# 33_PP0_CONFIG.net
KiCad netlist of a schematic drawn in Altium Designer
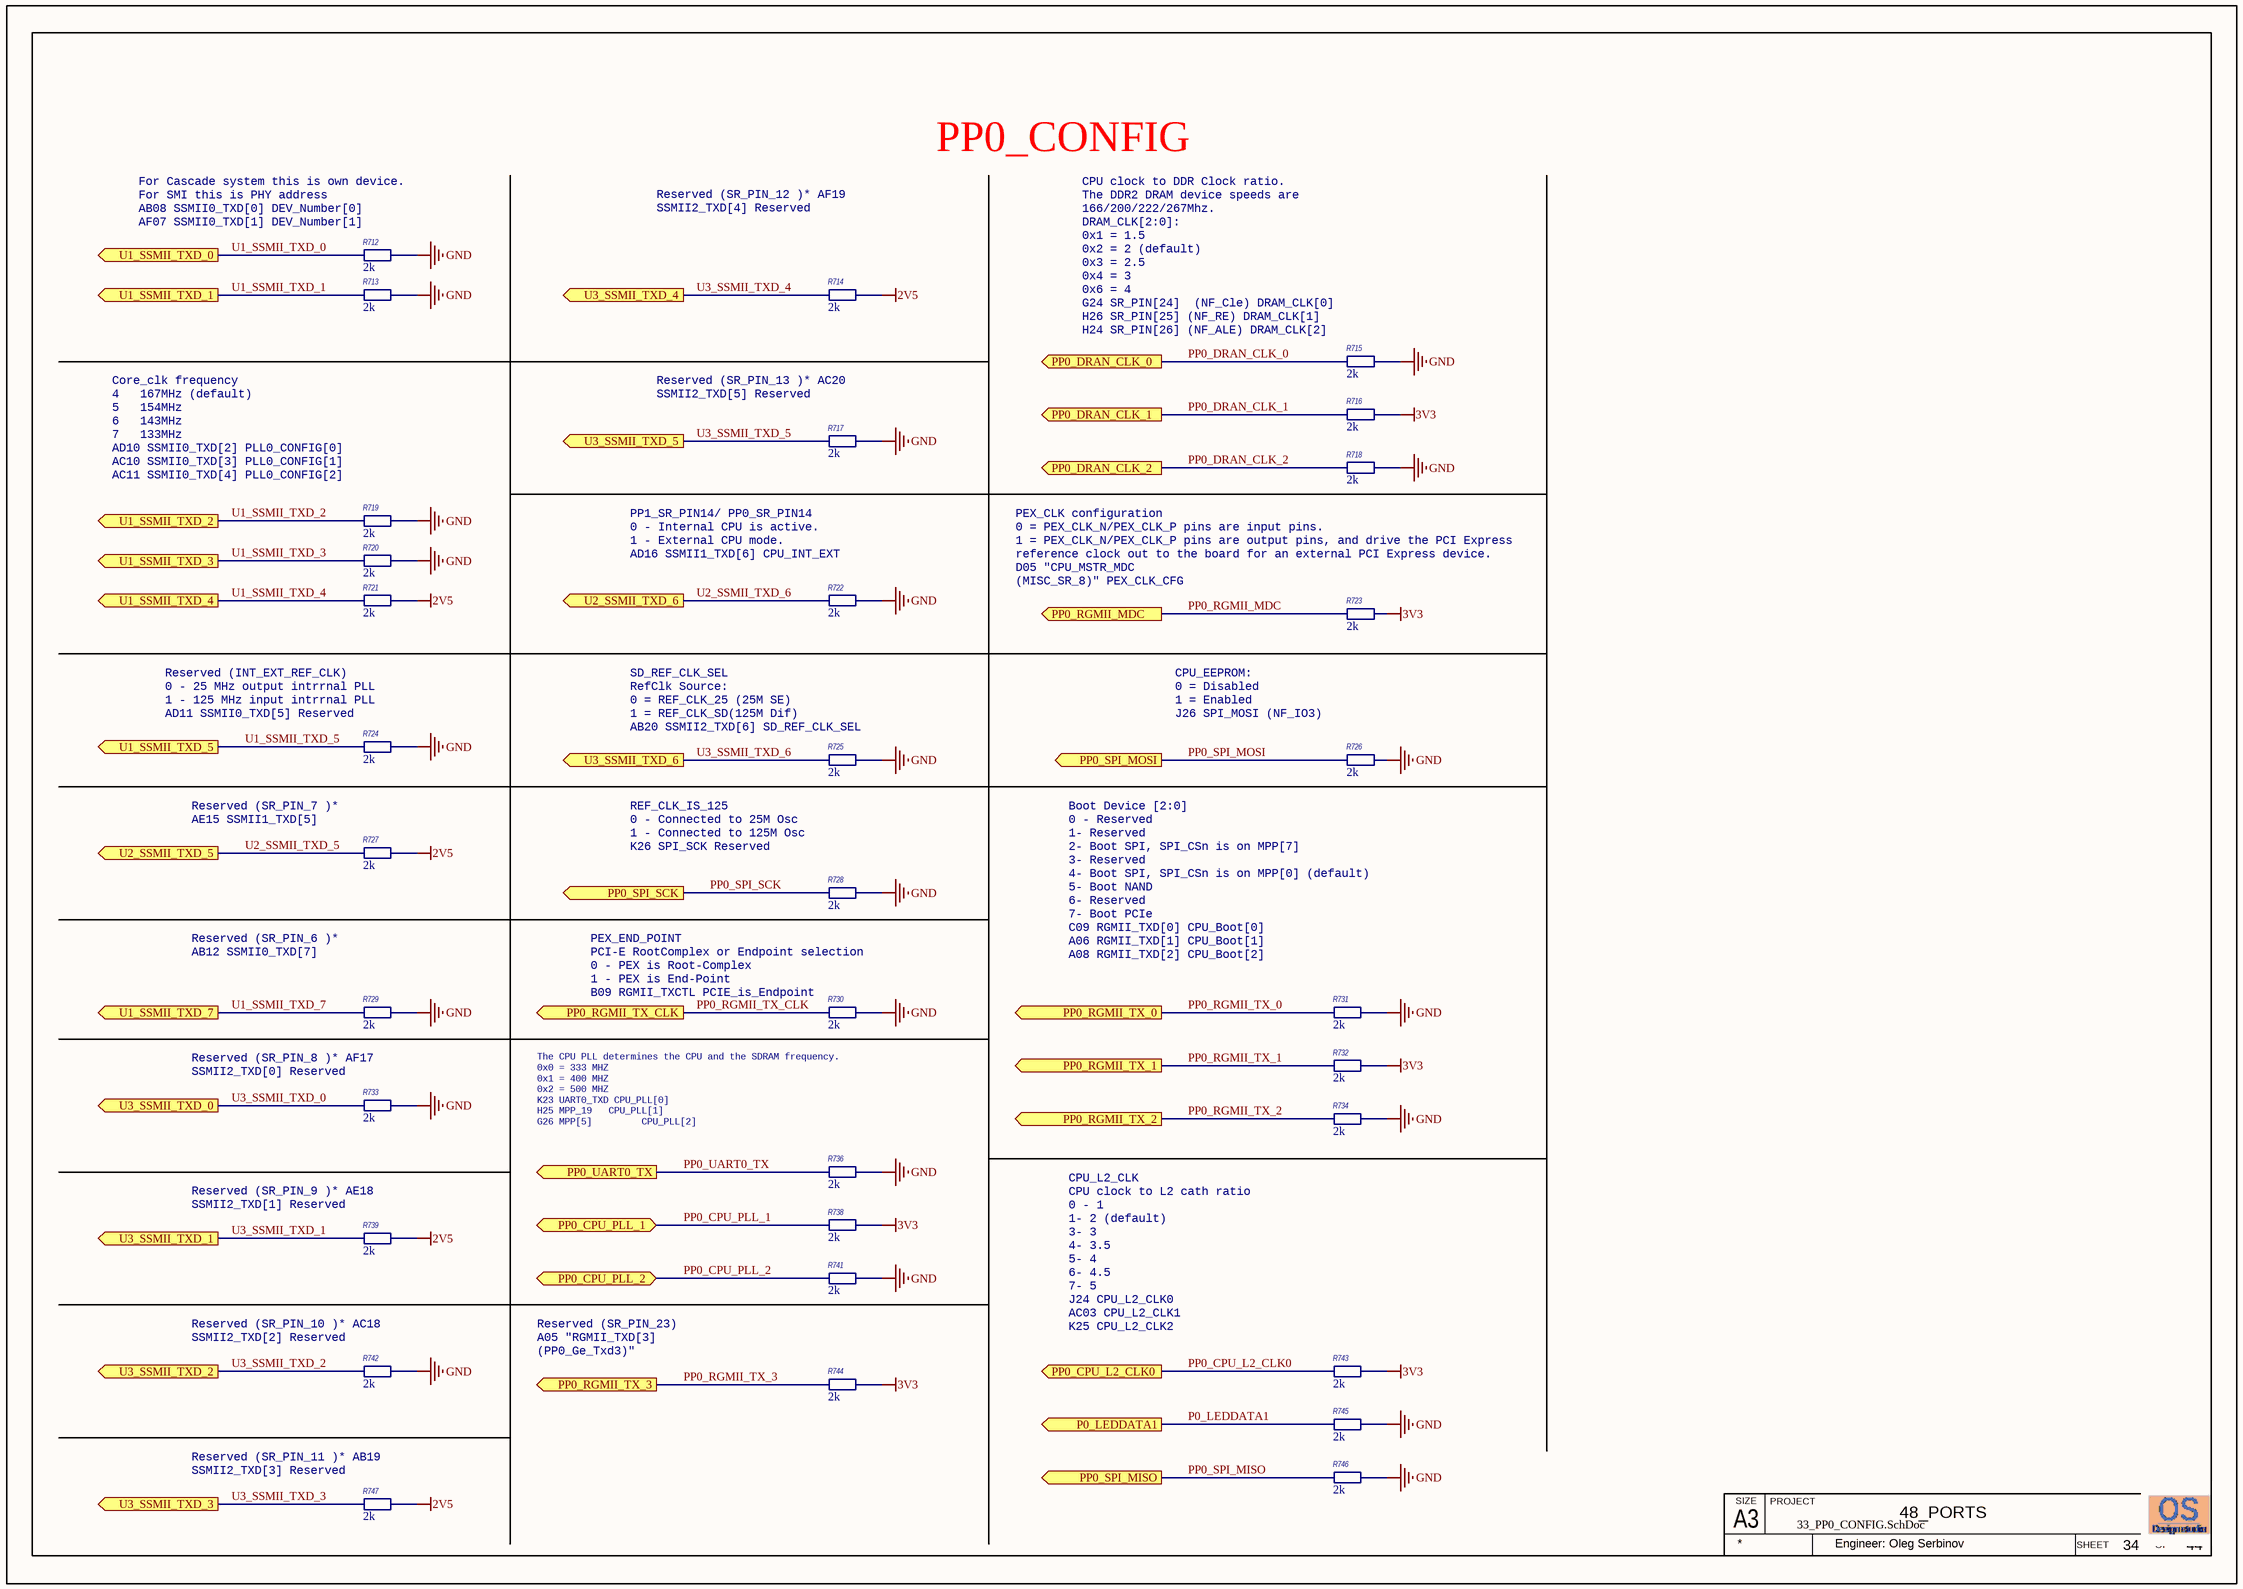
[diagram p0: 33_PP0_CONFIG.SchDoc]

(export (version "E")
  (design (tool "Eeschema 10.0.6"))
  (components
    (comp (ref "R712")
      (value "ERJ-2RKF2001X")
      (footprint "R0402_IPC High Density")
      (description "R0402, 2k 1%")
      (fields
        (field (name "TOLERANCE") "±1%")
        (field (name "MANUFACTURER") "Panasonic")
        (field (name "RESISTANCE (OHMS)") "2k")
      )
      (libsource (lib "RESISTOR") (part "ERJ-2RKF2001X"))
    )
    (comp (ref "R713")
      (value "ERJ-2RKF2001X")
      (footprint "R0402_IPC High Density")
      (description "R0402, 2k 1%")
      (fields
        (field (name "TOLERANCE") "±1%")
        (field (name "MANUFACTURER") "Panasonic")
        (field (name "RESISTANCE (OHMS)") "2k")
      )
      (libsource (lib "RESISTOR") (part "ERJ-2RKF2001X"))
    )
    (comp (ref "R714")
      (value "ERJ-2RKF2001X")
      (footprint "R0402_IPC High Density")
      (description "R0402, 2k 1%")
      (fields
        (field (name "TOLERANCE") "±1%")
        (field (name "MANUFACTURER") "Panasonic")
        (field (name "RESISTANCE (OHMS)") "2k")
      )
      (libsource (lib "RESISTOR") (part "ERJ-2RKF2001X"))
    )
    (comp (ref "R715")
      (value "ERJ-2RKF2001X")
      (footprint "R0402_IPC High Density")
      (description "R0402, 2k 1%")
      (fields
        (field (name "TOLERANCE") "±1%")
        (field (name "MANUFACTURER") "Panasonic")
        (field (name "RESISTANCE (OHMS)") "2k")
      )
      (libsource (lib "RESISTOR") (part "ERJ-2RKF2001X"))
    )
    (comp (ref "R716")
      (value "ERJ-2RKF2001X")
      (footprint "R0402_IPC High Density")
      (description "R0402, 2k 1%")
      (fields
        (field (name "TOLERANCE") "±1%")
        (field (name "MANUFACTURER") "Panasonic")
        (field (name "RESISTANCE (OHMS)") "2k")
      )
      (libsource (lib "RESISTOR") (part "ERJ-2RKF2001X"))
    )
    (comp (ref "R717")
      (value "ERJ-2RKF2001X")
      (footprint "R0402_IPC High Density")
      (description "R0402, 2k 1%")
      (fields
        (field (name "TOLERANCE") "±1%")
        (field (name "MANUFACTURER") "Panasonic")
        (field (name "RESISTANCE (OHMS)") "2k")
      )
      (libsource (lib "RESISTOR") (part "ERJ-2RKF2001X"))
    )
    (comp (ref "R718")
      (value "ERJ-2RKF2001X")
      (footprint "R0402_IPC High Density")
      (description "R0402, 2k 1%")
      (fields
        (field (name "TOLERANCE") "±1%")
        (field (name "MANUFACTURER") "Panasonic")
        (field (name "RESISTANCE (OHMS)") "2k")
      )
      (libsource (lib "RESISTOR") (part "ERJ-2RKF2001X"))
    )
    (comp (ref "R719")
      (value "ERJ-2RKF2001X")
      (footprint "R0402_IPC High Density")
      (description "R0402, 2k 1%")
      (fields
        (field (name "TOLERANCE") "±1%")
        (field (name "MANUFACTURER") "Panasonic")
        (field (name "RESISTANCE (OHMS)") "2k")
      )
      (libsource (lib "RESISTOR") (part "ERJ-2RKF2001X"))
    )
    (comp (ref "R720")
      (value "ERJ-2RKF2001X")
      (footprint "R0402_IPC High Density")
      (description "R0402, 2k 1%")
      (fields
        (field (name "TOLERANCE") "±1%")
        (field (name "MANUFACTURER") "Panasonic")
        (field (name "RESISTANCE (OHMS)") "2k")
      )
      (libsource (lib "RESISTOR") (part "ERJ-2RKF2001X"))
    )
    (comp (ref "R721")
      (value "ERJ-2RKF2001X")
      (footprint "R0402_IPC High Density")
      (description "R0402, 2k 1%")
      (fields
        (field (name "TOLERANCE") "±1%")
        (field (name "MANUFACTURER") "Panasonic")
        (field (name "RESISTANCE (OHMS)") "2k")
      )
      (libsource (lib "RESISTOR") (part "ERJ-2RKF2001X"))
    )
    (comp (ref "R722")
      (value "ERJ-2RKF2001X")
      (footprint "R0402_IPC High Density")
      (description "R0402, 2k 1%")
      (fields
        (field (name "TOLERANCE") "±1%")
        (field (name "MANUFACTURER") "Panasonic")
        (field (name "RESISTANCE (OHMS)") "2k")
      )
      (libsource (lib "RESISTOR") (part "ERJ-2RKF2001X"))
    )
    (comp (ref "R723")
      (value "ERJ-2RKF2001X")
      (footprint "R0402_IPC High Density")
      (description "R0402, 2k 1%")
      (fields
        (field (name "TOLERANCE") "±1%")
        (field (name "MANUFACTURER") "Panasonic")
        (field (name "RESISTANCE (OHMS)") "2k")
      )
      (libsource (lib "RESISTOR") (part "ERJ-2RKF2001X"))
    )
    (comp (ref "R724")
      (value "ERJ-2RKF2001X")
      (footprint "R0402_IPC High Density")
      (description "R0402, 2k 1%")
      (fields
        (field (name "TOLERANCE") "±1%")
        (field (name "MANUFACTURER") "Panasonic")
        (field (name "RESISTANCE (OHMS)") "2k")
      )
      (libsource (lib "RESISTOR") (part "ERJ-2RKF2001X"))
    )
    (comp (ref "R725")
      (value "ERJ-2RKF2001X")
      (footprint "R0402_IPC High Density")
      (description "R0402, 2k 1%")
      (fields
        (field (name "TOLERANCE") "±1%")
        (field (name "MANUFACTURER") "Panasonic")
        (field (name "RESISTANCE (OHMS)") "2k")
      )
      (libsource (lib "RESISTOR") (part "ERJ-2RKF2001X"))
    )
    (comp (ref "R726")
      (value "ERJ-2RKF2001X")
      (footprint "R0402_IPC High Density")
      (description "R0402, 2k 1%")
      (fields
        (field (name "TOLERANCE") "±1%")
        (field (name "MANUFACTURER") "Panasonic")
        (field (name "RESISTANCE (OHMS)") "2k")
      )
      (libsource (lib "RESISTOR") (part "ERJ-2RKF2001X"))
    )
    (comp (ref "R727")
      (value "ERJ-2RKF2001X")
      (footprint "R0402_IPC High Density")
      (description "R0402, 2k 1%")
      (fields
        (field (name "TOLERANCE") "±1%")
        (field (name "MANUFACTURER") "Panasonic")
        (field (name "RESISTANCE (OHMS)") "2k")
      )
      (libsource (lib "RESISTOR") (part "ERJ-2RKF2001X"))
    )
    (comp (ref "R728")
      (value "ERJ-2RKF2001X")
      (footprint "R0402_IPC High Density")
      (description "R0402, 2k 1%")
      (fields
        (field (name "TOLERANCE") "±1%")
        (field (name "MANUFACTURER") "Panasonic")
        (field (name "RESISTANCE (OHMS)") "2k")
      )
      (libsource (lib "RESISTOR") (part "ERJ-2RKF2001X"))
    )
    (comp (ref "R729")
      (value "ERJ-2RKF2001X")
      (footprint "R0402_IPC High Density")
      (description "R0402, 2k 1%")
      (fields
        (field (name "TOLERANCE") "±1%")
        (field (name "MANUFACTURER") "Panasonic")
        (field (name "RESISTANCE (OHMS)") "2k")
      )
      (libsource (lib "RESISTOR") (part "ERJ-2RKF2001X"))
    )
    (comp (ref "R730")
      (value "ERJ-2RKF2001X")
      (footprint "R0402_IPC High Density")
      (description "R0402, 2k 1%")
      (fields
        (field (name "TOLERANCE") "±1%")
        (field (name "MANUFACTURER") "Panasonic")
        (field (name "RESISTANCE (OHMS)") "2k")
      )
      (libsource (lib "RESISTOR") (part "ERJ-2RKF2001X"))
    )
    (comp (ref "R731")
      (value "ERJ-2RKF2001X")
      (footprint "R0402_IPC High Density")
      (description "R0402, 2k 1%")
      (fields
        (field (name "TOLERANCE") "±1%")
        (field (name "MANUFACTURER") "Panasonic")
        (field (name "RESISTANCE (OHMS)") "2k")
      )
      (libsource (lib "RESISTOR") (part "ERJ-2RKF2001X"))
    )
    (comp (ref "R732")
      (value "ERJ-2RKF2001X")
      (footprint "R0402_IPC High Density")
      (description "R0402, 2k 1%")
      (fields
        (field (name "TOLERANCE") "±1%")
        (field (name "MANUFACTURER") "Panasonic")
        (field (name "RESISTANCE (OHMS)") "2k")
      )
      (libsource (lib "RESISTOR") (part "ERJ-2RKF2001X"))
    )
    (comp (ref "R733")
      (value "ERJ-2RKF2001X")
      (footprint "R0402_IPC High Density")
      (description "R0402, 2k 1%")
      (fields
        (field (name "TOLERANCE") "±1%")
        (field (name "MANUFACTURER") "Panasonic")
        (field (name "RESISTANCE (OHMS)") "2k")
      )
      (libsource (lib "RESISTOR") (part "ERJ-2RKF2001X"))
    )
    (comp (ref "R734")
      (value "ERJ-2RKF2001X")
      (footprint "R0402_IPC High Density")
      (description "R0402, 2k 1%")
      (fields
        (field (name "TOLERANCE") "±1%")
        (field (name "MANUFACTURER") "Panasonic")
        (field (name "RESISTANCE (OHMS)") "2k")
      )
      (libsource (lib "RESISTOR") (part "ERJ-2RKF2001X"))
    )
    (comp (ref "R736")
      (value "ERJ-2RKF2001X")
      (footprint "R0402_IPC High Density")
      (description "R0402, 2k 1%")
      (fields
        (field (name "TOLERANCE") "±1%")
        (field (name "MANUFACTURER") "Panasonic")
        (field (name "RESISTANCE (OHMS)") "2k")
      )
      (libsource (lib "RESISTOR") (part "ERJ-2RKF2001X"))
    )
    (comp (ref "R738")
      (value "ERJ-2RKF2001X")
      (footprint "R0402_IPC High Density")
      (description "R0402, 2k 1%")
      (fields
        (field (name "TOLERANCE") "±1%")
        (field (name "MANUFACTURER") "Panasonic")
        (field (name "RESISTANCE (OHMS)") "2k")
      )
      (libsource (lib "RESISTOR") (part "ERJ-2RKF2001X"))
    )
    (comp (ref "R739")
      (value "ERJ-2RKF2001X")
      (footprint "R0402_IPC High Density")
      (description "R0402, 2k 1%")
      (fields
        (field (name "TOLERANCE") "±1%")
        (field (name "MANUFACTURER") "Panasonic")
        (field (name "RESISTANCE (OHMS)") "2k")
      )
      (libsource (lib "RESISTOR") (part "ERJ-2RKF2001X"))
    )
    (comp (ref "R741")
      (value "ERJ-2RKF2001X")
      (footprint "R0402_IPC High Density")
      (description "R0402, 2k 1%")
      (fields
        (field (name "TOLERANCE") "±1%")
        (field (name "MANUFACTURER") "Panasonic")
        (field (name "RESISTANCE (OHMS)") "2k")
      )
      (libsource (lib "RESISTOR") (part "ERJ-2RKF2001X"))
    )
    (comp (ref "R742")
      (value "ERJ-2RKF2001X")
      (footprint "R0402_IPC High Density")
      (description "R0402, 2k 1%")
      (fields
        (field (name "TOLERANCE") "±1%")
        (field (name "MANUFACTURER") "Panasonic")
        (field (name "RESISTANCE (OHMS)") "2k")
      )
      (libsource (lib "RESISTOR") (part "ERJ-2RKF2001X"))
    )
    (comp (ref "R743")
      (value "ERJ-2RKF2001X")
      (footprint "R0402_IPC High Density")
      (description "R0402, 2k 1%")
      (fields
        (field (name "TOLERANCE") "±1%")
        (field (name "MANUFACTURER") "Panasonic")
        (field (name "RESISTANCE (OHMS)") "2k")
      )
      (libsource (lib "RESISTOR") (part "ERJ-2RKF2001X"))
    )
    (comp (ref "R744")
      (value "ERJ-2RKF2001X")
      (footprint "R0402_IPC High Density")
      (description "R0402, 2k 1%")
      (fields
        (field (name "TOLERANCE") "±1%")
        (field (name "MANUFACTURER") "Panasonic")
        (field (name "RESISTANCE (OHMS)") "2k")
      )
      (libsource (lib "RESISTOR") (part "ERJ-2RKF2001X"))
    )
    (comp (ref "R745")
      (value "ERJ-2RKF2001X")
      (footprint "R0402_IPC High Density")
      (description "R0402, 2k 1%")
      (fields
        (field (name "TOLERANCE") "±1%")
        (field (name "MANUFACTURER") "Panasonic")
        (field (name "RESISTANCE (OHMS)") "2k")
      )
      (libsource (lib "RESISTOR") (part "ERJ-2RKF2001X"))
    )
    (comp (ref "R746")
      (value "ERJ-2RKF2001X")
      (footprint "R0402_IPC High Density")
      (description "R0402, 2k 1%")
      (fields
        (field (name "TOLERANCE") "±1%")
        (field (name "MANUFACTURER") "Panasonic")
        (field (name "RESISTANCE (OHMS)") "2k")
      )
      (libsource (lib "RESISTOR") (part "ERJ-2RKF2001X"))
    )
    (comp (ref "R747")
      (value "ERJ-2RKF2001X")
      (footprint "R0402_IPC High Density")
      (description "R0402, 2k 1%")
      (fields
        (field (name "TOLERANCE") "±1%")
        (field (name "MANUFACTURER") "Panasonic")
        (field (name "RESISTANCE (OHMS)") "2k")
      )
      (libsource (lib "RESISTOR") (part "ERJ-2RKF2001X"))
    )
  )
  (nets
    (net (code "1") (name "/P0_LEDDATA1") (class "Default") (node (ref "R745") (pin "1") (pintype "passive")))
    (net (code "2") (name "/PP0_CPU_L2_CLK0") (class "Default")
      (node (ref "R743") (pin "1") (pintype "passive"))
    )
    (net (code "3") (name "/PP0_CPU_PLL_1") (class "Default")
      (node (ref "R738") (pin "1") (pintype "passive"))
    )
    (net (code "4") (name "/PP0_CPU_PLL_2") (class "Default")
      (node (ref "R741") (pin "1") (pintype "passive"))
    )
    (net (code "5") (name "/PP0_DRAN_CLK_0") (class "Default")
      (node (ref "R715") (pin "1") (pintype "passive"))
    )
    (net (code "6") (name "/PP0_DRAN_CLK_1") (class "Default")
      (node (ref "R716") (pin "1") (pintype "passive"))
    )
    (net (code "7") (name "/PP0_DRAN_CLK_2") (class "Default")
      (node (ref "R718") (pin "1") (pintype "passive"))
    )
    (net (code "8") (name "/PP0_RGMII_MDC") (class "Default")
      (node (ref "R723") (pin "1") (pintype "passive"))
    )
    (net (code "9") (name "/PP0_RGMII_TX_0") (class "Default")
      (node (ref "R731") (pin "1") (pintype "passive"))
    )
    (net (code "10") (name "/PP0_RGMII_TX_1") (class "Default")
      (node (ref "R732") (pin "1") (pintype "passive"))
    )
    (net (code "11") (name "/PP0_RGMII_TX_2") (class "Default")
      (node (ref "R734") (pin "1") (pintype "passive"))
    )
    (net (code "12") (name "/PP0_RGMII_TX_3") (class "Default")
      (node (ref "R744") (pin "1") (pintype "passive"))
    )
    (net (code "13") (name "/PP0_RGMII_TX_CLK") (class "Default")
      (node (ref "R730") (pin "1") (pintype "passive"))
    )
    (net (code "14") (name "/PP0_SPI_MISO") (class "Default")
      (node (ref "R746") (pin "1") (pintype "passive"))
    )
    (net (code "15") (name "/PP0_SPI_MOSI") (class "Default")
      (node (ref "R726") (pin "1") (pintype "passive"))
    )
    (net (code "16") (name "/PP0_SPI_SCK") (class "Default")
      (node (ref "R728") (pin "1") (pintype "passive"))
    )
    (net (code "17") (name "/PP0_UART0_TX") (class "Default")
      (node (ref "R736") (pin "1") (pintype "passive"))
    )
    (net (code "18") (name "/U1_SSMII_TXD_0") (class "Default")
      (node (ref "R712") (pin "1") (pintype "passive"))
    )
    (net (code "19") (name "/U1_SSMII_TXD_1") (class "Default")
      (node (ref "R713") (pin "1") (pintype "passive"))
    )
    (net (code "20") (name "/U1_SSMII_TXD_2") (class "Default")
      (node (ref "R719") (pin "1") (pintype "passive"))
    )
    (net (code "21") (name "/U1_SSMII_TXD_3") (class "Default")
      (node (ref "R720") (pin "1") (pintype "passive"))
    )
    (net (code "22") (name "/U1_SSMII_TXD_4") (class "Default")
      (node (ref "R721") (pin "1") (pintype "passive"))
    )
    (net (code "23") (name "/U1_SSMII_TXD_5") (class "Default")
      (node (ref "R724") (pin "1") (pintype "passive"))
    )
    (net (code "24") (name "/U1_SSMII_TXD_7") (class "Default")
      (node (ref "R729") (pin "1") (pintype "passive"))
    )
    (net (code "25") (name "/U2_SSMII_TXD_5") (class "Default")
      (node (ref "R727") (pin "1") (pintype "passive"))
    )
    (net (code "26") (name "/U2_SSMII_TXD_6") (class "Default")
      (node (ref "R722") (pin "1") (pintype "passive"))
    )
    (net (code "27") (name "/U3_SSMII_TXD_0") (class "Default")
      (node (ref "R733") (pin "1") (pintype "passive"))
    )
    (net (code "28") (name "/U3_SSMII_TXD_1") (class "Default")
      (node (ref "R739") (pin "1") (pintype "passive"))
    )
    (net (code "29") (name "/U3_SSMII_TXD_2") (class "Default")
      (node (ref "R742") (pin "1") (pintype "passive"))
    )
    (net (code "30") (name "/U3_SSMII_TXD_3") (class "Default")
      (node (ref "R747") (pin "1") (pintype "passive"))
    )
    (net (code "31") (name "/U3_SSMII_TXD_4") (class "Default")
      (node (ref "R714") (pin "1") (pintype "passive"))
    )
    (net (code "32") (name "/U3_SSMII_TXD_5") (class "Default")
      (node (ref "R717") (pin "1") (pintype "passive"))
    )
    (net (code "33") (name "/U3_SSMII_TXD_6") (class "Default")
      (node (ref "R725") (pin "1") (pintype "passive"))
    )
    (net (code "34") (name "2V5") (class "Default")
      (node (ref "R714") (pin "2") (pintype "passive"))
      (node (ref "R721") (pin "2") (pintype "passive"))
      (node (ref "R727") (pin "2") (pintype "passive"))
      (node (ref "R739") (pin "2") (pintype "passive"))
      (node (ref "R747") (pin "2") (pintype "passive"))
    )
    (net (code "35") (name "3V3") (class "Default")
      (node (ref "R716") (pin "2") (pintype "passive"))
      (node (ref "R723") (pin "2") (pintype "passive"))
      (node (ref "R732") (pin "2") (pintype "passive"))
      (node (ref "R738") (pin "2") (pintype "passive"))
      (node (ref "R743") (pin "2") (pintype "passive"))
      (node (ref "R744") (pin "2") (pintype "passive"))
    )
    (net (code "36") (name "GND") (class "Default")
      (node (ref "R712") (pin "2") (pintype "passive"))
      (node (ref "R713") (pin "2") (pintype "passive"))
      (node (ref "R715") (pin "2") (pintype "passive"))
      (node (ref "R717") (pin "2") (pintype "passive"))
      (node (ref "R718") (pin "2") (pintype "passive"))
      (node (ref "R719") (pin "2") (pintype "passive"))
      (node (ref "R720") (pin "2") (pintype "passive"))
      (node (ref "R722") (pin "2") (pintype "passive"))
      (node (ref "R724") (pin "2") (pintype "passive"))
      (node (ref "R725") (pin "2") (pintype "passive"))
      (node (ref "R726") (pin "2") (pintype "passive"))
      (node (ref "R728") (pin "2") (pintype "passive"))
      (node (ref "R729") (pin "2") (pintype "passive"))
      (node (ref "R730") (pin "2") (pintype "passive"))
      (node (ref "R731") (pin "2") (pintype "passive"))
      (node (ref "R733") (pin "2") (pintype "passive"))
      (node (ref "R734") (pin "2") (pintype "passive"))
      (node (ref "R736") (pin "2") (pintype "passive"))
      (node (ref "R741") (pin "2") (pintype "passive"))
      (node (ref "R742") (pin "2") (pintype "passive"))
      (node (ref "R745") (pin "2") (pintype "passive"))
      (node (ref "R746") (pin "2") (pintype "passive"))
    )
  )
)
